# LoopFilterWaveyRadar.net
KiCad netlist of a schematic drawn in Altium Designer
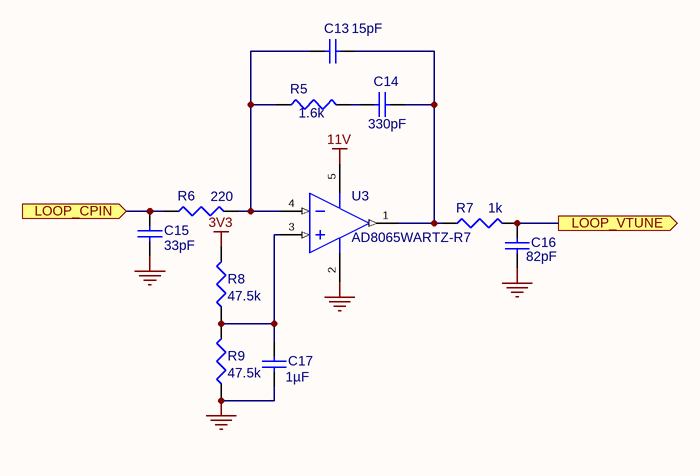
[diagram p0: LoopFilterWaveyRadar.SchDoc]

(export (version "E")
  (design (tool "Eeschema 10.0.6"))
  (components
    (comp (ref "C13")
      (value "15pF")
      (footprint "CAPC1005X56X25LL10T15")
      (description "Cap Ceramic 15pF 50V C0G 5% SMD 0402 125C T/R")
      (fields (field (name "Comment") "04025A150JAT2A"))
      (libsource (lib "University of South Florida") (part "CAP-NP-2"))
    )
    (comp (ref "C14")
      (value "330pF")
      (footprint "FP-GRM155-0_05-MFG")
      (description "MURATA - GRM1555C1H331JA01D - CERAMIC CAPACITOR 330PF 50V, C0G, 5%, 0402")
      (fields (field (name "Comment") "GRM1555C1H331JA01D"))
      (libsource (lib "University of South Florida") (part "CAP-NP-2"))
    )
    (comp (ref "C15")
      (value "33pF")
      (footprint "CAPC1005X56X25LL10T15")
      (fields (field (name "Comment") "04025A330JAT2A"))
      (libsource (lib "University of South Florida") (part "CAP-NP-2"))
    )
    (comp (ref "C16")
      (value "82pF")
      (footprint "CAPC1005X56X25LL10T15")
      (description "Multilayer Ceramic Capacitors MLCC - SMD/SMT 50V 82pF C0G 0402 1% Tol")
      (fields (field (name "Comment") "04025A820FAT2A"))
      (libsource (lib "University of South Florida") (part "CAP-NP-2"))
    )
    (comp (ref "C17")
      (value "1µF")
      (footprint "CAPC0402(1005)60_L")
      (description "Chip Capacitor, 1µF +/-20%, 10V, 0402, Thickness 0.6 mm")
      (fields (field (name "TOLERANCE") "10%") (field (name "Comment") "Capacitor 1µF +/-20% 10V 0402"))
      (libsource (lib "University of South Florida") (part "CAP-NP-2"))
    )
    (comp (ref "R5")
      (value "1.6k")
      (footprint "RESC0402(1005)_L")
      (description "Chip Resistor, 1,6 kOhms, +/-5 %, 63 mW, -55 to 155 degC, 0402")
      (fields (field (name "POWER") "63mW") (field (name "TOLERANCE") "5%"))
      (libsource (lib "University of South Florida") (part "RES-2"))
    )
    (comp (ref "R6")
      (value "220")
      (footprint "RESC1005X40X25NL05T05")
      (description "PANASONIC ELECTRONIC COMPONENTS - ERJ2RKF2200X - RES, THICK FILM, 220R, 1%, 0.1W, 0402")
      (fields (field (name "Comment") "ERJ-2RKF2200X"))
      (libsource (lib "University of South Florida") (part "ResistorSymbol"))
    )
    (comp (ref "R7")
      (value "1k")
      (footprint "RESC1005X40X25ML05T05")
      (description "Chip Resistor, 1 KOhm, +/- 1%, 0.1 W, -55 to 155 degC, 0402 (1005 Metric)")
      (fields (field (name "POWER") "100mW") (field (name "TOLERANCE") "1%"))
      (libsource (lib "University of South Florida") (part "ResistorSymbol"))
    )
    (comp (ref "R8")
      (value "47.5k")
      (footprint "RESC0402(1005)_L")
      (description "Chip Resistor, 47,5 kOhms, +/-1 %, 63 mW, -55 to 155 degC, 0402")
      (fields (field (name "TOLERANCE") "1%") (field (name "POWER") "63mW"))
      (libsource (lib "University of South Florida") (part "RES-2"))
    )
    (comp (ref "R9")
      (value "47.5k")
      (footprint "RESC0402(1005)_L")
      (description "Chip Resistor, 47,5 kOhms, +/-1 %, 63 mW, -55 to 155 degC, 0402")
      (fields (field (name "TOLERANCE") "1%") (field (name "POWER") "63mW"))
      (libsource (lib "University of South Florida") (part "RES-2"))
    )
    (comp (ref "U3")
      (value "AD8065WARTZ-R7")
      (footprint "ADI-RJ-5_N")
      (description "Op Amp Single High Performance Amplifier R-R O/P ±5V/10V Automotive 5-Pin SOT-23 T/R")
      (libsource (lib "University of South Florida") (part "ADI-AD8065-RJ-5"))
    )
  )
  (nets
    (net (code "1") (name "/LOOP_CPIN") (class "Default")
      (node (ref "C15") (pin "2") (pinfunction "2_2") (pintype "passive"))
      (node (ref "R6") (pin "1") (pinfunction "1_1") (pintype "passive"))
    )
    (net (code "2") (name "/LOOP_VTUNE") (class "Default")
      (node (ref "C16") (pin "1") (pinfunction "1_1") (pintype "passive"))
      (node (ref "R7") (pin "2") (pinfunction "2_2") (pintype "passive"))
    )
    (net (code "3") (name "3V3") (class "Default")
      (node (ref "R8") (pin "2") (pinfunction "2_2") (pintype "passive"))
    )
    (net (code "4") (name "11V") (class "Default")
      (node (ref "U3") (pin "5") (pinfunction "+VS_5") (pintype "power_in"))
    )
    (net (code "5") (name "GND") (class "Default")
      (node (ref "C15") (pin "1") (pinfunction "1_1") (pintype "passive"))
      (node (ref "C16") (pin "2") (pinfunction "2_2") (pintype "passive"))
      (node (ref "C17") (pin "2") (pinfunction "2_2") (pintype "passive"))
      (node (ref "R9") (pin "1") (pinfunction "1_1") (pintype "passive"))
      (node (ref "U3") (pin "2") (pinfunction "-VS_2") (pintype "power_in"))
    )
    (net (code "6") (name "Net-(C14-Pad1)") (class "Default")
      (node (ref "C14") (pin "1") (pinfunction "1_1") (pintype "passive"))
      (node (ref "R5") (pin "2") (pinfunction "2_2") (pintype "passive"))
    )
    (net (code "7") (name "Net-(U3-+IN)") (class "Default")
      (node (ref "C17") (pin "1") (pinfunction "1_1") (pintype "passive"))
      (node (ref "R8") (pin "1") (pinfunction "1_1") (pintype "passive"))
      (node (ref "R9") (pin "2") (pinfunction "2_2") (pintype "passive"))
      (node (ref "U3") (pin "3") (pinfunction "+IN_3") (pintype "input"))
    )
    (net (code "8") (name "Net-(U3--IN)") (class "Default")
      (node (ref "C13") (pin "1") (pinfunction "1_1") (pintype "passive"))
      (node (ref "R5") (pin "1") (pinfunction "1_1") (pintype "passive"))
      (node (ref "R6") (pin "2") (pinfunction "2_2") (pintype "passive"))
      (node (ref "U3") (pin "4") (pinfunction "-IN_4") (pintype "input"))
    )
    (net (code "9") (name "Net-(U3-VOUT)") (class "Default")
      (node (ref "C13") (pin "2") (pinfunction "2_2") (pintype "passive"))
      (node (ref "C14") (pin "2") (pinfunction "2_2") (pintype "passive"))
      (node (ref "R7") (pin "1") (pinfunction "1_1") (pintype "passive"))
      (node (ref "U3") (pin "1") (pinfunction "VOUT_1") (pintype "output"))
    )
  )
)
